# 8_imu_debug_conn.net
KiCad netlist of a schematic drawn in Altium Designer
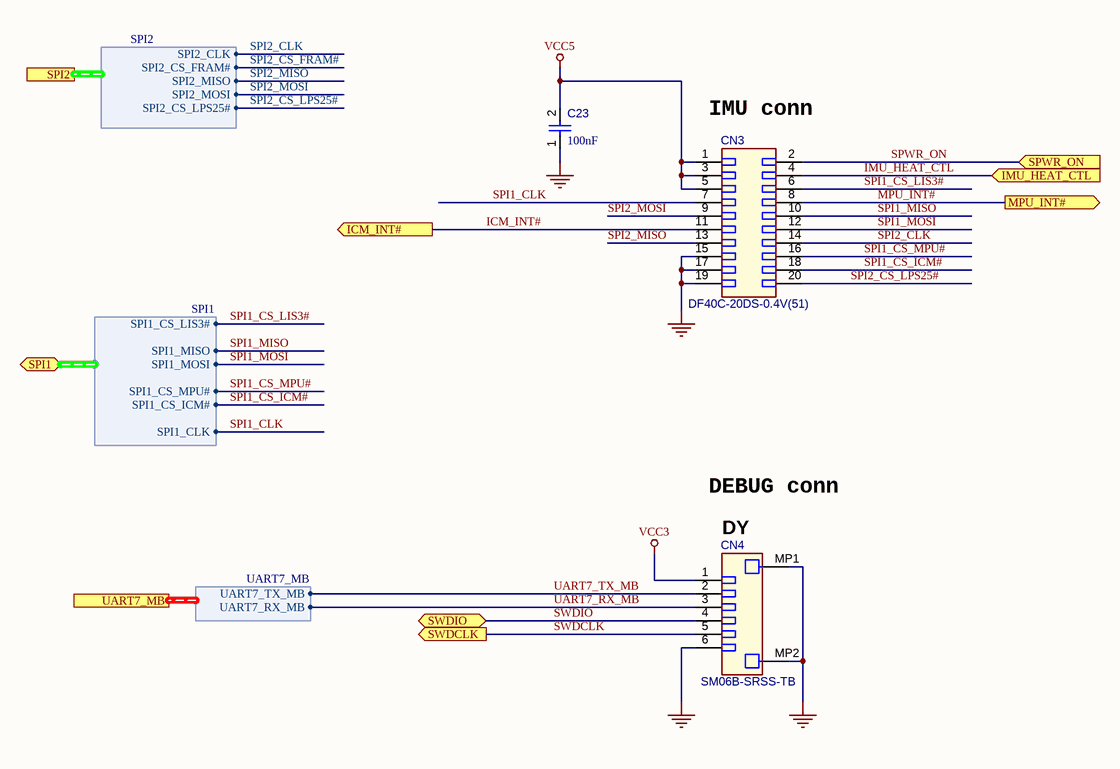
[diagram p0:  8_imu_debug_conn.SchDoc]

(export (version "E")
  (design (tool "Eeschema 10.0.6"))
  (components
    (comp (ref "C23")
      (value "100nF")
      (footprint "CAPC0402(1005)60_L")
      (description "Chip Capacitor, 100nF +/-20%, 10V, 0402, Thickness 0.6 mm")
      (fields (field (name "TOLERANCE") "20%") (field (name "Comment") "Capacitor 100nF +/-20% 10V 0402"))
      (libsource (lib "MHH -  Altium Advanced Course A365 01") (part "CAP-NP-2"))
    )
    (comp (ref "CN3")
      (value "DF40C-20DS-0.4V(51)")
      (footprint "HIRO-DF40C-20DS-0.4V(51)_V")
      (description "Receptacle Connector, 30 V, 0.3 A, -35 to 85 degC, RoHS, Tape and Reel")
      (libsource (lib "MHH -  Altium Advanced Course A365 01") (part "CMP-00114-7"))
    )
    (comp (ref "CN4")
      (value "SM06B-SRSS-TB")
      (footprint "JST-SM06B-SRSS-TB_V")
      (description "Male Header, Pitch 1 mm, 1 x 6 Position, Height 2.95 mm, -25 to 85 degC, RoHS, Tape and Reel")
      (libsource (lib "MHH -  Altium Advanced Course A365 01") (part "CMP-00143-5"))
    )
  )
  (nets
    (net (code "4") (name "/ICM_INT#") (class "Default")
      (node (ref "CN3") (pin "11") (pinfunction "11_11") (pintype "passive"))
    )
    (net (code "5") (name "/IMU_HEAT_CTL") (class "Default")
      (node (ref "CN3") (pin "4") (pinfunction "4_4") (pintype "passive"))
    )
    (net (code "6") (name "/MPU_INT#") (class "Default")
      (node (ref "CN3") (pin "8") (pinfunction "8_8") (pintype "passive"))
    )
    (net (code "7") (name "/SPI1_CLK") (class "Default")
      (node (ref "CN3") (pin "7") (pinfunction "7_7") (pintype "passive"))
    )
    (net (code "8") (name "/SPI1_CS_ICM#") (class "Default")
      (node (ref "CN3") (pin "18") (pinfunction "18_18") (pintype "passive"))
    )
    (net (code "9") (name "/SPI1_CS_LIS3#") (class "Default")
      (node (ref "CN3") (pin "6") (pinfunction "6_6") (pintype "passive"))
    )
    (net (code "10") (name "/SPI1_CS_MPU#") (class "Default")
      (node (ref "CN3") (pin "16") (pinfunction "16_16") (pintype "passive"))
    )
    (net (code "11") (name "/SPI1_MISO") (class "Default")
      (node (ref "CN3") (pin "10") (pinfunction "10_10") (pintype "passive"))
    )
    (net (code "12") (name "/SPI1_MOSI") (class "Default")
      (node (ref "CN3") (pin "12") (pinfunction "12_12") (pintype "passive"))
    )
    (net (code "13") (name "/SPI2_CLK") (class "Default")
      (node (ref "CN3") (pin "14") (pinfunction "14_14") (pintype "passive"))
    )
    (net (code "15") (name "/SPI2_CS_LPS25#") (class "Default")
      (node (ref "CN3") (pin "20") (pinfunction "20_20") (pintype "passive"))
    )
    (net (code "16") (name "/SPI2_MISO") (class "Default")
      (node (ref "CN3") (pin "13") (pinfunction "13_13") (pintype "passive"))
    )
    (net (code "17") (name "/SPI2_MOSI") (class "Default")
      (node (ref "CN3") (pin "9") (pinfunction "9_9") (pintype "passive"))
    )
    (net (code "18") (name "/SPWR_ON") (class "Default")
      (node (ref "CN3") (pin "2") (pinfunction "2_2") (pintype "passive"))
    )
    (net (code "19") (name "/SWDCLK") (class "Default")
      (node (ref "CN4") (pin "5") (pinfunction "5_5") (pintype "passive"))
    )
    (net (code "20") (name "/SWDIO") (class "Default")
      (node (ref "CN4") (pin "4") (pinfunction "4_4") (pintype "passive"))
    )
    (net (code "21") (name "/UART7_RX_MB") (class "Default")
      (node (ref "CN4") (pin "3") (pinfunction "3_3") (pintype "passive"))
    )
    (net (code "22") (name "/UART7_TX_MB") (class "Default")
      (node (ref "CN4") (pin "2") (pinfunction "2_2") (pintype "passive"))
    )
    (net (code "26") (name "GND") (class "Default")
      (node (ref "C23") (pin "1") (pinfunction "1_1") (pintype "passive"))
      (node (ref "CN3") (pin "15") (pinfunction "15_15") (pintype "passive"))
      (node (ref "CN3") (pin "17") (pinfunction "17_17") (pintype "passive"))
      (node (ref "CN3") (pin "19") (pinfunction "19_19") (pintype "passive"))
      (node (ref "CN4") (pin "6") (pinfunction "6_6") (pintype "passive"))
      (node (ref "CN4") (pin "MP1") (pinfunction "MP1_MP1") (pintype "passive"))
      (node (ref "CN4") (pin "MP2") (pinfunction "MP2_MP2") (pintype "passive"))
    )
    (net (code "27") (name "VCC3") (class "Default")
      (node (ref "CN4") (pin "1") (pinfunction "1_1") (pintype "passive"))
    )
    (net (code "28") (name "VCC5") (class "Default")
      (node (ref "C23") (pin "2") (pinfunction "2_2") (pintype "passive"))
      (node (ref "CN3") (pin "1") (pinfunction "1_1") (pintype "passive"))
      (node (ref "CN3") (pin "3") (pinfunction "3_3") (pintype "passive"))
      (node (ref "CN3") (pin "5") (pinfunction "5_5") (pintype "passive"))
    )
  )
)
